# MCU_hall_crossboard_1_1.net
KiCad netlist of a schematic drawn in Altium Designer
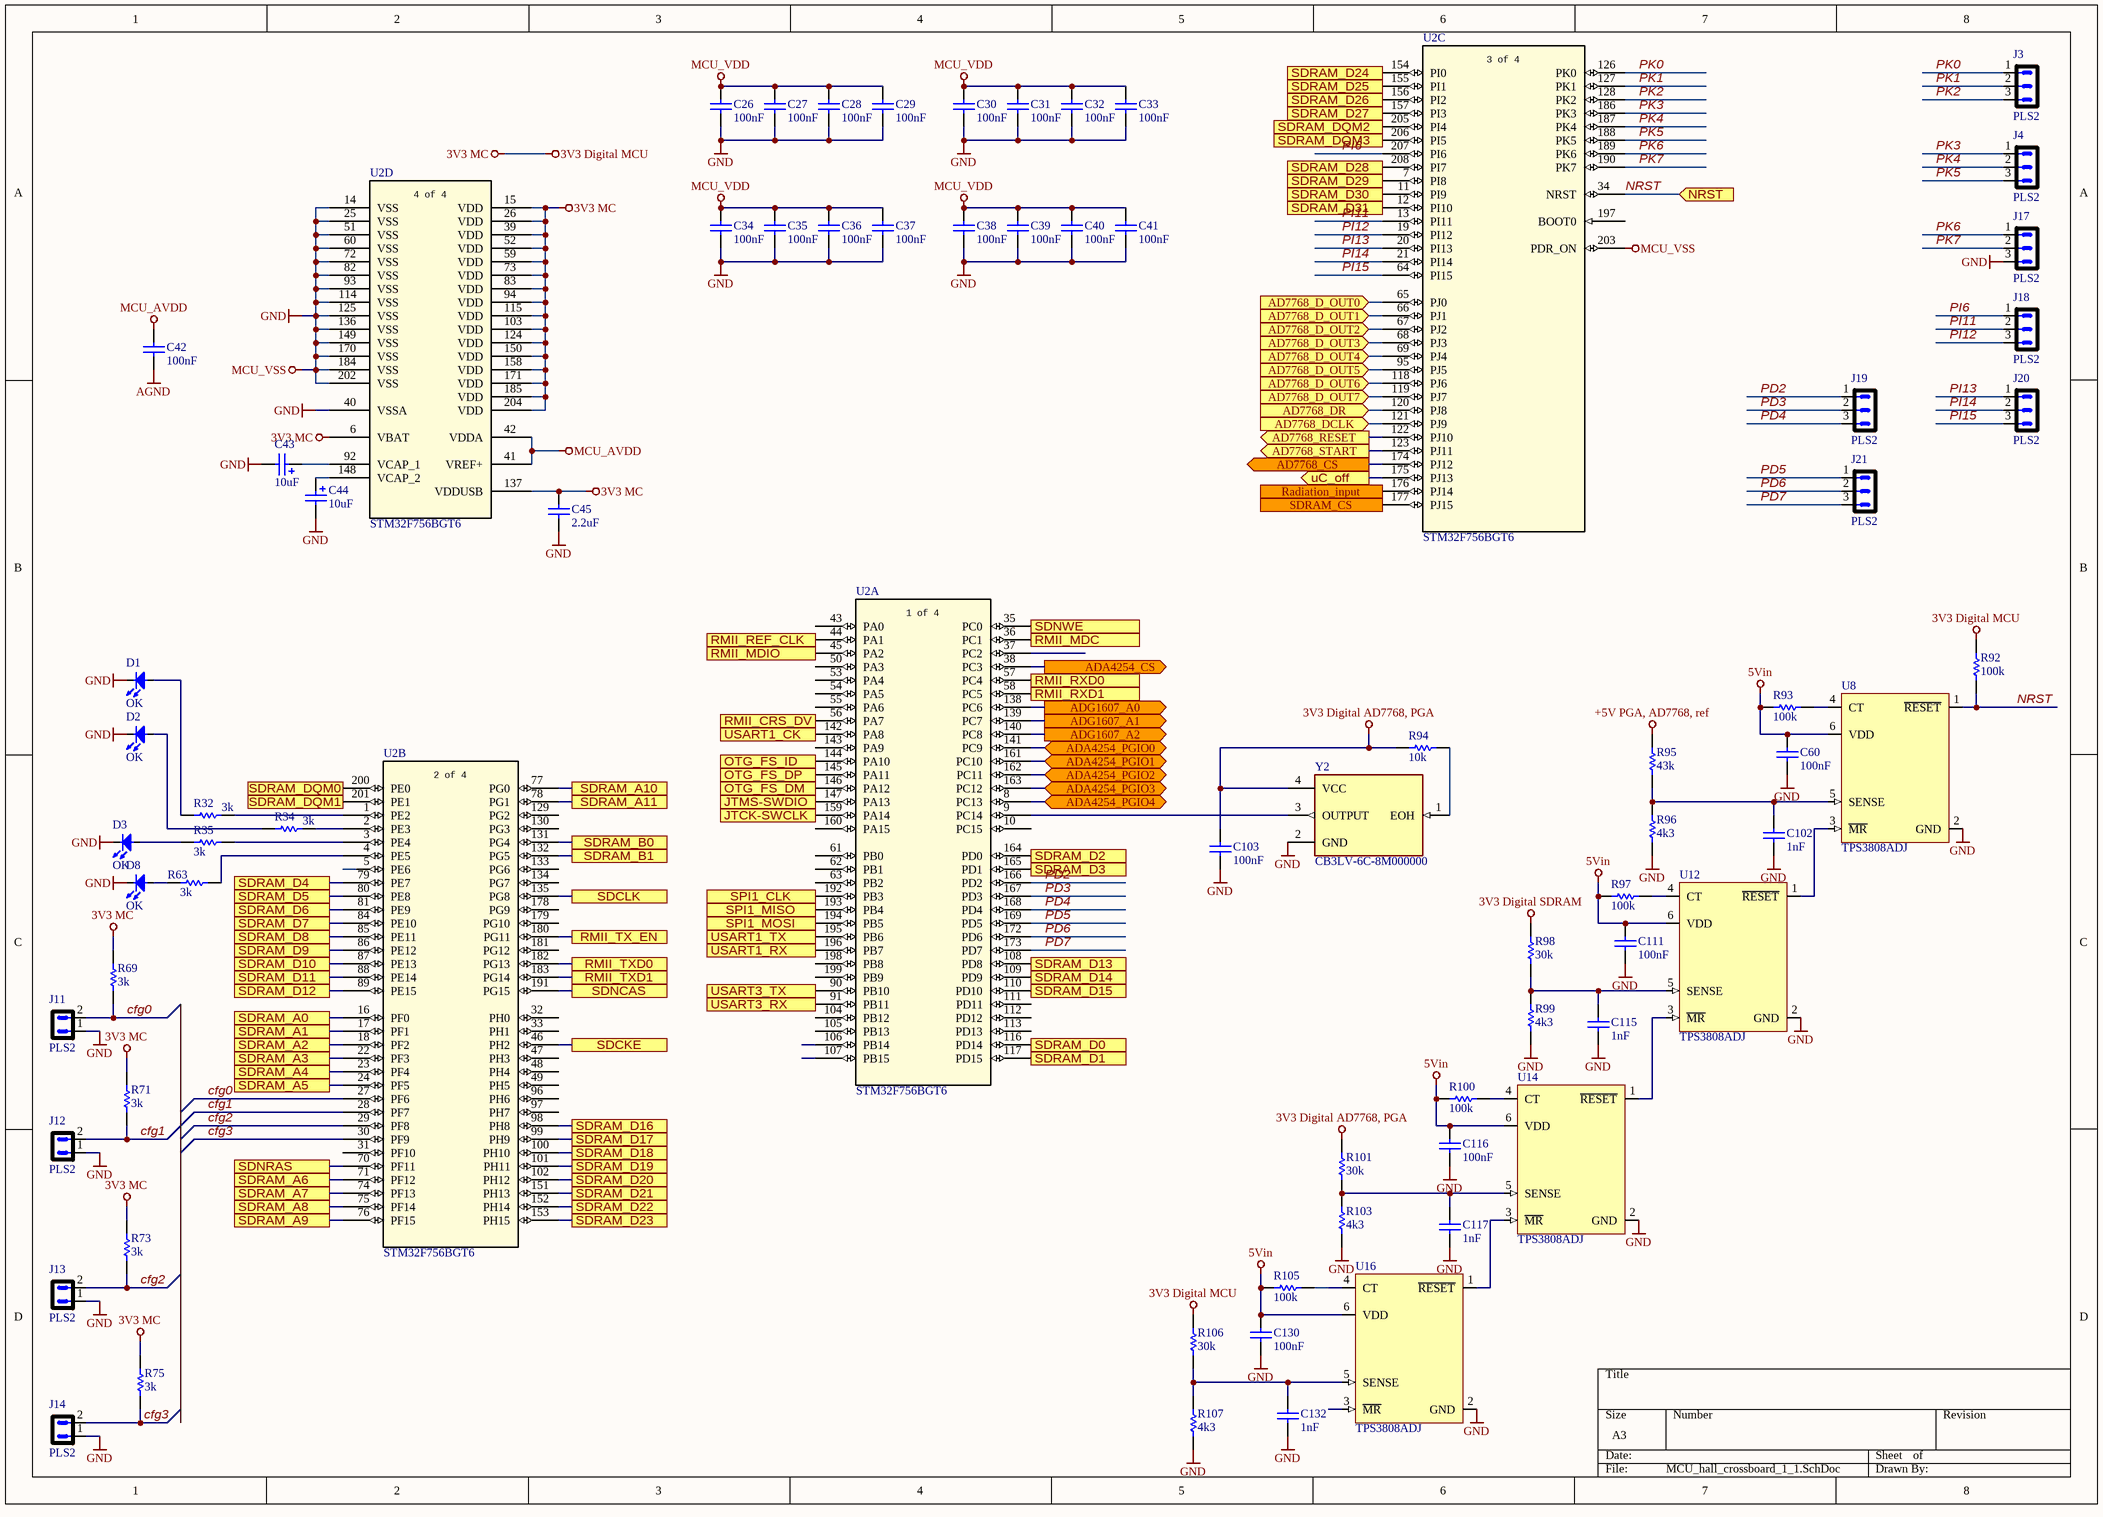
[diagram p0: MCU_hall_crossboard_1_1.SchDoc]

(export (version "E")
  (design (tool "Eeschema 10.0.6"))
  (components
    (comp (ref "C26")
      (value "100nF")
      (footprint "hall_crossboard_1_1_library:0603C")
      (description "Capacitor 0402 / 0603 / 0805")
      (libsource (lib "hall_crossboard_1_1_library") (part "Capacitor_ST"))
    )
    (comp (ref "C27")
      (value "100nF")
      (footprint "hall_crossboard_1_1_library:0603C")
      (description "Capacitor 0402 / 0603 / 0805")
      (libsource (lib "hall_crossboard_1_1_library") (part "Capacitor_ST"))
    )
    (comp (ref "C28")
      (value "100nF")
      (footprint "hall_crossboard_1_1_library:0603C")
      (description "Capacitor 0402 / 0603 / 0805")
      (libsource (lib "hall_crossboard_1_1_library") (part "Capacitor_ST"))
    )
    (comp (ref "C29")
      (value "100nF")
      (footprint "hall_crossboard_1_1_library:0603C")
      (description "Capacitor 0402 / 0603 / 0805")
      (libsource (lib "hall_crossboard_1_1_library") (part "Capacitor_ST"))
    )
    (comp (ref "C30")
      (value "100nF")
      (footprint "hall_crossboard_1_1_library:0603C")
      (description "Capacitor 0402 / 0603 / 0805")
      (libsource (lib "hall_crossboard_1_1_library") (part "Capacitor_ST"))
    )
    (comp (ref "C31")
      (value "100nF")
      (footprint "hall_crossboard_1_1_library:0603C")
      (description "Capacitor 0402 / 0603 / 0805")
      (libsource (lib "hall_crossboard_1_1_library") (part "Capacitor_ST"))
    )
    (comp (ref "C32")
      (value "100nF")
      (footprint "hall_crossboard_1_1_library:0603C")
      (description "Capacitor 0402 / 0603 / 0805")
      (libsource (lib "hall_crossboard_1_1_library") (part "Capacitor_ST"))
    )
    (comp (ref "C33")
      (value "100nF")
      (footprint "hall_crossboard_1_1_library:0603C")
      (description "Capacitor 0402 / 0603 / 0805")
      (libsource (lib "hall_crossboard_1_1_library") (part "Capacitor_ST"))
    )
    (comp (ref "C34")
      (value "100nF")
      (footprint "hall_crossboard_1_1_library:0603C")
      (description "Capacitor 0402 / 0603 / 0805")
      (libsource (lib "hall_crossboard_1_1_library") (part "Capacitor_ST"))
    )
    (comp (ref "C35")
      (value "100nF")
      (footprint "hall_crossboard_1_1_library:0603C")
      (description "Capacitor 0402 / 0603 / 0805")
      (libsource (lib "hall_crossboard_1_1_library") (part "Capacitor_ST"))
    )
    (comp (ref "C36")
      (value "100nF")
      (footprint "hall_crossboard_1_1_library:0603C")
      (description "Capacitor 0402 / 0603 / 0805")
      (libsource (lib "hall_crossboard_1_1_library") (part "Capacitor_ST"))
    )
    (comp (ref "C37")
      (value "100nF")
      (footprint "hall_crossboard_1_1_library:0603C")
      (description "Capacitor 0402 / 0603 / 0805")
      (libsource (lib "hall_crossboard_1_1_library") (part "Capacitor_ST"))
    )
    (comp (ref "C38")
      (value "100nF")
      (footprint "hall_crossboard_1_1_library:0603C")
      (description "Capacitor 0402 / 0603 / 0805")
      (libsource (lib "hall_crossboard_1_1_library") (part "Capacitor_ST"))
    )
    (comp (ref "C39")
      (value "100nF")
      (footprint "hall_crossboard_1_1_library:0603C")
      (description "Capacitor 0402 / 0603 / 0805")
      (libsource (lib "hall_crossboard_1_1_library") (part "Capacitor_ST"))
    )
    (comp (ref "C40")
      (value "100nF")
      (footprint "hall_crossboard_1_1_library:0603C")
      (description "Capacitor 0402 / 0603 / 0805")
      (libsource (lib "hall_crossboard_1_1_library") (part "Capacitor_ST"))
    )
    (comp (ref "C41")
      (value "100nF")
      (footprint "hall_crossboard_1_1_library:0603C")
      (description "Capacitor 0402 / 0603 / 0805")
      (libsource (lib "hall_crossboard_1_1_library") (part "Capacitor_ST"))
    )
    (comp (ref "C42")
      (value "100nF")
      (footprint "hall_crossboard_1_1_library:0603C")
      (description "Capacitor 0402 / 0603 / 0805")
      (libsource (lib "hall_crossboard_1_1_library") (part "Capacitor_ST"))
    )
    (comp (ref "C43")
      (value "10uF")
      (footprint "hall_crossboard_1_1_library:0805C")
      (description "Polarized Capacitor,10uF,10V,10%,typeA,VISHAY")
      (libsource (lib "hall_crossboard_1_1_library") (part "Cap_10uF_POL_10%_TANA"))
    )
    (comp (ref "C44")
      (value "10uF")
      (footprint "hall_crossboard_1_1_library:0805C")
      (description "Polarized Capacitor,10uF,10V,10%,typeA,VISHAY")
      (libsource (lib "hall_crossboard_1_1_library") (part "Cap_10uF_POL_10%_TANA"))
    )
    (comp (ref "C45")
      (value "2.2uF")
      (footprint "hall_crossboard_1_1_library:0805C")
      (description "Capacitor 0402 / 0603 / 0805")
      (libsource (lib "hall_crossboard_1_1_library") (part "Capacitor_ST"))
    )
    (comp (ref "C60")
      (value "100nF")
      (footprint "hall_crossboard_1_1_library:0603C")
      (description "Capacitor 0402 / 0603 / 0805")
      (libsource (lib "hall_crossboard_1_1_library") (part "Capacitor_ST"))
    )
    (comp (ref "C102")
      (value "1nF")
      (footprint "hall_crossboard_1_1_library:0603C")
      (description "Capacitor 0402 / 0603 / 0805")
      (libsource (lib "hall_crossboard_1_1_library") (part "Capacitor_ST"))
    )
    (comp (ref "C103")
      (value "100nF")
      (footprint "hall_crossboard_1_1_library:0603C")
      (description "Capacitor 0402 / 0603 / 0805")
      (libsource (lib "hall_crossboard_1_1_library") (part "Capacitor_ST"))
    )
    (comp (ref "C111")
      (value "100nF")
      (footprint "hall_crossboard_1_1_library:0603C")
      (description "Capacitor 0402 / 0603 / 0805")
      (libsource (lib "hall_crossboard_1_1_library") (part "Capacitor_ST"))
    )
    (comp (ref "C115")
      (value "1nF")
      (footprint "hall_crossboard_1_1_library:0603C")
      (description "Capacitor 0402 / 0603 / 0805")
      (libsource (lib "hall_crossboard_1_1_library") (part "Capacitor_ST"))
    )
    (comp (ref "C116")
      (value "100nF")
      (footprint "hall_crossboard_1_1_library:0603C")
      (description "Capacitor 0402 / 0603 / 0805")
      (libsource (lib "hall_crossboard_1_1_library") (part "Capacitor_ST"))
    )
    (comp (ref "C117")
      (value "1nF")
      (footprint "hall_crossboard_1_1_library:0603C")
      (description "Capacitor 0402 / 0603 / 0805")
      (libsource (lib "hall_crossboard_1_1_library") (part "Capacitor_ST"))
    )
    (comp (ref "C130")
      (value "100nF")
      (footprint "hall_crossboard_1_1_library:0603C")
      (description "Capacitor 0402 / 0603 / 0805")
      (libsource (lib "hall_crossboard_1_1_library") (part "Capacitor_ST"))
    )
    (comp (ref "C132")
      (value "1nF")
      (footprint "hall_crossboard_1_1_library:0603C")
      (description "Capacitor 0402 / 0603 / 0805")
      (libsource (lib "hall_crossboard_1_1_library") (part "Capacitor_ST"))
    )
    (comp (ref "D1")
      (value "OK")
      (footprint "LED0603")
      (description "Чип светодиод 0603")
      (libsource (lib "schematic_hall_crossboard_1_1_library") (part "LED0603"))
    )
    (comp (ref "D2")
      (value "OK")
      (footprint "LED0603")
      (description "Чип светодиод 0603")
      (libsource (lib "schematic_hall_crossboard_1_1_library") (part "LED0603"))
    )
    (comp (ref "D3")
      (value "OK")
      (footprint "LED0603")
      (description "Чип светодиод 0603")
      (libsource (lib "schematic_hall_crossboard_1_1_library") (part "LED0603"))
    )
    (comp (ref "D8")
      (value "OK")
      (footprint "LED0603")
      (description "Чип светодиод 0603")
      (libsource (lib "schematic_hall_crossboard_1_1_library") (part "LED0603"))
    )
    (comp (ref "J3")
      (value "PLS2")
      (footprint "COMATEL_385.0358.1.03.400")
      (description "PLS3")
      (libsource (lib "hall_crossboard_1_1") (part "PLS3"))
    )
    (comp (ref "J4")
      (value "PLS2")
      (footprint "COMATEL_385.0358.1.03.400")
      (description "PLS3")
      (libsource (lib "hall_crossboard_1_1") (part "PLS3"))
    )
    (comp (ref "J11")
      (value "PLS2")
      (footprint "SAMTEC_TSW-102-23-L-S")
      (libsource (lib "hall_crossboard_1_1_library") (part "PLS2"))
    )
    (comp (ref "J12")
      (value "PLS2")
      (footprint "SAMTEC_TSW-102-23-L-S")
      (libsource (lib "hall_crossboard_1_1_library") (part "PLS2"))
    )
    (comp (ref "J13")
      (value "PLS2")
      (footprint "SAMTEC_TSW-102-23-L-S")
      (libsource (lib "hall_crossboard_1_1_library") (part "PLS2"))
    )
    (comp (ref "J14")
      (value "PLS2")
      (footprint "SAMTEC_TSW-102-23-L-S")
      (libsource (lib "hall_crossboard_1_1_library") (part "PLS2"))
    )
    (comp (ref "J17")
      (value "PLS2")
      (footprint "COMATEL_385.0358.1.03.400")
      (description "PLS3")
      (libsource (lib "hall_crossboard_1_1") (part "PLS3"))
    )
    (comp (ref "J18")
      (value "PLS2")
      (footprint "COMATEL_385.0358.1.03.400")
      (description "PLS3")
      (libsource (lib "hall_crossboard_1_1") (part "PLS3"))
    )
    (comp (ref "J19")
      (value "PLS2")
      (footprint "COMATEL_385.0358.1.03.400")
      (description "PLS3")
      (libsource (lib "hall_crossboard_1_1") (part "PLS3"))
    )
    (comp (ref "J20")
      (value "PLS2")
      (footprint "COMATEL_385.0358.1.03.400")
      (description "PLS3")
      (libsource (lib "hall_crossboard_1_1") (part "PLS3"))
    )
    (comp (ref "J21")
      (value "PLS2")
      (footprint "COMATEL_385.0358.1.03.400")
      (description "PLS3")
      (libsource (lib "hall_crossboard_1_1") (part "PLS3"))
    )
    (comp (ref "R32")
      (value "3k")
      (footprint "0603R")
      (description "Resistor 0402 / 0603 / 0805")
      (libsource (lib "hall_crossboard_1_1_library") (part "Resistor_ST"))
    )
    (comp (ref "R34")
      (value "3k")
      (footprint "0603R")
      (description "Resistor 0402 / 0603 / 0805")
      (libsource (lib "hall_crossboard_1_1_library") (part "Resistor_ST"))
    )
    (comp (ref "R35")
      (value "3k")
      (footprint "0603R")
      (description "Resistor 0402 / 0603 / 0805")
      (libsource (lib "hall_crossboard_1_1_library") (part "Resistor_ST"))
    )
    (comp (ref "R63")
      (value "3k")
      (footprint "0603R")
      (description "Resistor 0402 / 0603 / 0805")
      (libsource (lib "hall_crossboard_1_1_library") (part "Resistor_ST"))
    )
    (comp (ref "R69")
      (value "3k")
      (footprint "0603R")
      (description "Resistor 0402 / 0603 / 0805")
      (libsource (lib "hall_crossboard_1_1_library") (part "Resistor_ST"))
    )
    (comp (ref "R71")
      (value "3k")
      (footprint "0603R")
      (description "Resistor 0402 / 0603 / 0805")
      (libsource (lib "hall_crossboard_1_1_library") (part "Resistor_ST"))
    )
    (comp (ref "R73")
      (value "3k")
      (footprint "0603R")
      (description "Resistor 0402 / 0603 / 0805")
      (libsource (lib "hall_crossboard_1_1_library") (part "Resistor_ST"))
    )
    (comp (ref "R75")
      (value "3k")
      (footprint "0603R")
      (description "Resistor 0402 / 0603 / 0805")
      (libsource (lib "hall_crossboard_1_1_library") (part "Resistor_ST"))
    )
    (comp (ref "R92")
      (value "100k")
      (footprint "0805R")
      (description "Resistor 0402 / 0603 / 0805")
      (libsource (lib "hall_crossboard_1_1_library") (part "Resistor_ST"))
    )
    (comp (ref "R93")
      (value "100k")
      (footprint "0805R")
      (description "Resistor 0402 / 0603 / 0805")
      (libsource (lib "hall_crossboard_1_1_library") (part "Resistor_ST"))
    )
    (comp (ref "R94")
      (value "10k")
      (footprint "0805R")
      (description "Resistor 0402 / 0603 / 0805 c2")
      (libsource (lib "hall_crossboard_1_1") (part "Resistor_ST"))
    )
    (comp (ref "R95")
      (value "43k")
      (footprint "0805R")
      (description "Resistor 0402 / 0603 / 0805")
      (libsource (lib "hall_crossboard_1_1_library") (part "Resistor_ST"))
    )
    (comp (ref "R96")
      (value "4k3")
      (footprint "0805R")
      (description "Resistor 0402 / 0603 / 0805")
      (libsource (lib "hall_crossboard_1_1_library") (part "Resistor_ST"))
    )
    (comp (ref "R97")
      (value "100k")
      (footprint "0805R")
      (description "Resistor 0402 / 0603 / 0805")
      (libsource (lib "hall_crossboard_1_1_library") (part "Resistor_ST"))
    )
    (comp (ref "R98")
      (value "30k")
      (footprint "0805R")
      (description "Resistor 0402 / 0603 / 0805")
      (libsource (lib "hall_crossboard_1_1_library") (part "Resistor_ST"))
    )
    (comp (ref "R99")
      (value "4k3")
      (footprint "0805R")
      (description "Resistor 0402 / 0603 / 0805")
      (libsource (lib "hall_crossboard_1_1_library") (part "Resistor_ST"))
    )
    (comp (ref "R100")
      (value "100k")
      (footprint "0805R")
      (description "Resistor 0402 / 0603 / 0805")
      (libsource (lib "hall_crossboard_1_1_library") (part "Resistor_ST"))
    )
    (comp (ref "R101")
      (value "30k")
      (footprint "0805R")
      (description "Resistor 0402 / 0603 / 0805")
      (libsource (lib "hall_crossboard_1_1_library") (part "Resistor_ST"))
    )
    (comp (ref "R103")
      (value "4k3")
      (footprint "0805R")
      (description "Resistor 0402 / 0603 / 0805")
      (libsource (lib "hall_crossboard_1_1_library") (part "Resistor_ST"))
    )
    (comp (ref "R105")
      (value "100k")
      (footprint "0805R")
      (description "Resistor 0402 / 0603 / 0805")
      (libsource (lib "hall_crossboard_1_1_library") (part "Resistor_ST"))
    )
    (comp (ref "R106")
      (value "30k")
      (footprint "0805R")
      (description "Resistor 0402 / 0603 / 0805")
      (libsource (lib "hall_crossboard_1_1_library") (part "Resistor_ST"))
    )
    (comp (ref "R107")
      (value "4k3")
      (footprint "0805R")
      (description "Resistor 0402 / 0603 / 0805")
      (libsource (lib "hall_crossboard_1_1_library") (part "Resistor_ST"))
    )
    (comp (ref "U2")
      (value "STM32F756BGT6")
      (footprint "footprint_hall_crossboard_1_1_library:QFP50P3000X3000X160-208N")
      (description "No Description Available")
      (libsource (lib "schematic_hall_crossboard_1_1_library") (part "STM32F756BGT6"))
    )
    (comp (ref "U8")
      (value "TPS3808ADJ")
      (footprint "footprint_hall_crossboard_1_1_library:SOT95P270X145-6N")
      (description "Supervisory Circuit. Low-Quiescent-Current, Programmable-Delay")
      (libsource (lib "schematic_hall_crossboard_1_1_library") (part "TPS3808"))
    )
    (comp (ref "U12")
      (value "TPS3808ADJ")
      (footprint "footprint_hall_crossboard_1_1_library:SOT95P270X145-6N")
      (description "Supervisory Circuit. Low-Quiescent-Current, Programmable-Delay")
      (libsource (lib "schematic_hall_crossboard_1_1_library") (part "TPS3808"))
    )
    (comp (ref "U14")
      (value "TPS3808ADJ")
      (footprint "footprint_hall_crossboard_1_1_library:SOT95P270X145-6N")
      (description "Supervisory Circuit. Low-Quiescent-Current, Programmable-Delay")
      (libsource (lib "schematic_hall_crossboard_1_1_library") (part "TPS3808"))
    )
    (comp (ref "U16")
      (value "TPS3808ADJ")
      (footprint "footprint_hall_crossboard_1_1_library:SOT95P270X145-6N")
      (description "Supervisory Circuit. Low-Quiescent-Current, Programmable-Delay")
      (libsource (lib "schematic_hall_crossboard_1_1_library") (part "TPS3808"))
    )
    (comp (ref "Y2")
      (value "CB3LV-6C-8M000000")
      (footprint "OSC_CB3LV-6C-8M000000")
      (description "8 MHz XO (Standard) HCMOS, TTL Oscillator 3.3V Enable/Disable 4-SMD, No Lead")
      (fields (field (name "MF") "CTS-Frequency Controls"))
      (libsource (lib "hall_crossboard_1_1") (part "CB3LV-6C-8M000000"))
    )
  )
  (nets
    (net (code "1") (name "+5V PGA, AD7768, ref") (class "Default")
      (node (ref "R95") (pin "2") (pinfunction "2_2") (pintype "passive"))
    )
    (net (code "2") (name "/AD7768_CS") (class "Default")
      (node (ref "U2") (pin "174") (pinfunction "PJ12_174") (pintype "bidirectional"))
    )
    (net (code "3") (name "/AD7768_DCLK") (class "Default")
      (node (ref "U2") (pin "121") (pinfunction "PJ9_121") (pintype "bidirectional"))
    )
    (net (code "4") (name "/AD7768_DR") (class "Default")
      (node (ref "U2") (pin "120") (pinfunction "PJ8_120") (pintype "bidirectional"))
    )
    (net (code "5") (name "/AD7768_D_OUT0") (class "Default")
      (node (ref "U2") (pin "65") (pinfunction "PJ0_65") (pintype "bidirectional"))
    )
    (net (code "6") (name "/AD7768_D_OUT1") (class "Default")
      (node (ref "U2") (pin "66") (pinfunction "PJ1_66") (pintype "bidirectional"))
    )
    (net (code "7") (name "/AD7768_D_OUT2") (class "Default")
      (node (ref "U2") (pin "67") (pinfunction "PJ2_67") (pintype "bidirectional"))
    )
    (net (code "8") (name "/AD7768_D_OUT3") (class "Default")
      (node (ref "U2") (pin "68") (pinfunction "PJ3_68") (pintype "bidirectional"))
    )
    (net (code "9") (name "/AD7768_D_OUT4") (class "Default")
      (node (ref "U2") (pin "69") (pinfunction "PJ4_69") (pintype "bidirectional"))
    )
    (net (code "10") (name "/AD7768_D_OUT5") (class "Default")
      (node (ref "U2") (pin "95") (pinfunction "PJ5_95") (pintype "bidirectional"))
    )
    (net (code "11") (name "/AD7768_D_OUT6") (class "Default")
      (node (ref "U2") (pin "118") (pinfunction "PJ6_118") (pintype "bidirectional"))
    )
    (net (code "12") (name "/AD7768_D_OUT7") (class "Default")
      (node (ref "U2") (pin "119") (pinfunction "PJ7_119") (pintype "bidirectional"))
    )
    (net (code "13") (name "/AD7768_RESET") (class "Default")
      (node (ref "U2") (pin "122") (pinfunction "PJ10_122") (pintype "bidirectional"))
    )
    (net (code "14") (name "/AD7768_START") (class "Default")
      (node (ref "U2") (pin "123") (pinfunction "PJ11_123") (pintype "bidirectional"))
    )
    (net (code "15") (name "/ADA4254_CS") (class "Default")
      (node (ref "U2") (pin "38") (pinfunction "PC3_38") (pintype "bidirectional"))
    )
    (net (code "16") (name "/ADA4254_PGIO0") (class "Default")
      (node (ref "U2") (pin "141") (pinfunction "PC9_141") (pintype "bidirectional"))
    )
    (net (code "17") (name "/ADA4254_PGIO1") (class "Default")
      (node (ref "U2") (pin "161") (pinfunction "PC10_161") (pintype "bidirectional"))
    )
    (net (code "18") (name "/ADA4254_PGIO2") (class "Default")
      (node (ref "U2") (pin "162") (pinfunction "PC11_162") (pintype "bidirectional"))
    )
    (net (code "19") (name "/ADA4254_PGIO3") (class "Default")
      (node (ref "U2") (pin "163") (pinfunction "PC12_163") (pintype "bidirectional"))
    )
    (net (code "20") (name "/ADA4254_PGIO4") (class "Default")
      (node (ref "U2") (pin "8") (pinfunction "PC13_8") (pintype "bidirectional"))
    )
    (net (code "21") (name "/ADG1607_A0") (class "Default")
      (node (ref "U2") (pin "138") (pinfunction "PC6_138") (pintype "bidirectional"))
    )
    (net (code "22") (name "/ADG1607_A1") (class "Default")
      (node (ref "U2") (pin "139") (pinfunction "PC7_139") (pintype "bidirectional"))
    )
    (net (code "23") (name "/ADG1607_A2") (class "Default")
      (node (ref "U2") (pin "140") (pinfunction "PC8_140") (pintype "bidirectional"))
    )
    (net (code "24") (name "/JTCK-SWCLK") (class "Default")
      (node (ref "U2") (pin "159") (pinfunction "PA14_159") (pintype "bidirectional"))
    )
    (net (code "25") (name "/JTMS-SWDIO") (class "Default")
      (node (ref "U2") (pin "147") (pinfunction "PA13_147") (pintype "bidirectional"))
    )
    (net (code "26") (name "/NRST") (class "Default")
      (node (ref "R92") (pin "1") (pinfunction "1_1") (pintype "passive"))
      (node (ref "U2") (pin "34") (pinfunction "NRST_34") (pintype "bidirectional"))
      (node (ref "U8") (pin "1") (pinfunction "~{RESET}_1") (pintype "open_collector"))
    )
    (net (code "27") (name "/OTG_FS_DM") (class "Default")
      (node (ref "U2") (pin "146") (pinfunction "PA12_146") (pintype "bidirectional"))
    )
    (net (code "28") (name "/OTG_FS_DP") (class "Default")
      (node (ref "U2") (pin "145") (pinfunction "PA11_145") (pintype "bidirectional"))
    )
    (net (code "29") (name "/OTG_FS_ID") (class "Default")
      (node (ref "U2") (pin "144") (pinfunction "PA10_144") (pintype "bidirectional"))
    )
    (net (code "30") (name "/PD2") (class "Default")
      (node (ref "J19") (pin "1") (pinfunction "1_1") (pintype "bidirectional"))
      (node (ref "U2") (pin "166") (pinfunction "PD2_166") (pintype "bidirectional"))
    )
    (net (code "31") (name "/PD3") (class "Default")
      (node (ref "J19") (pin "2") (pinfunction "2_2") (pintype "bidirectional"))
      (node (ref "U2") (pin "167") (pinfunction "PD3_167") (pintype "bidirectional"))
    )
    (net (code "32") (name "/PD4") (class "Default")
      (node (ref "J19") (pin "3") (pinfunction "3_3") (pintype "bidirectional"))
      (node (ref "U2") (pin "168") (pinfunction "PD4_168") (pintype "bidirectional"))
    )
    (net (code "33") (name "/PD5") (class "Default")
      (node (ref "J21") (pin "1") (pinfunction "1_1") (pintype "bidirectional"))
      (node (ref "U2") (pin "169") (pinfunction "PD5_169") (pintype "bidirectional"))
    )
    (net (code "34") (name "/PD6") (class "Default")
      (node (ref "J21") (pin "2") (pinfunction "2_2") (pintype "bidirectional"))
      (node (ref "U2") (pin "172") (pinfunction "PD6_172") (pintype "bidirectional"))
    )
    (net (code "35") (name "/PD7") (class "Default")
      (node (ref "J21") (pin "3") (pinfunction "3_3") (pintype "bidirectional"))
      (node (ref "U2") (pin "173") (pinfunction "PD7_173") (pintype "bidirectional"))
    )
    (net (code "36") (name "/PI6") (class "Default")
      (node (ref "J18") (pin "1") (pinfunction "1_1") (pintype "bidirectional"))
      (node (ref "U2") (pin "207") (pinfunction "PI6_207") (pintype "bidirectional"))
    )
    (net (code "37") (name "/PI11") (class "Default")
      (node (ref "J18") (pin "2") (pinfunction "2_2") (pintype "bidirectional"))
      (node (ref "U2") (pin "13") (pinfunction "PI11_13") (pintype "bidirectional"))
    )
    (net (code "38") (name "/PI12") (class "Default")
      (node (ref "J18") (pin "3") (pinfunction "3_3") (pintype "bidirectional"))
      (node (ref "U2") (pin "19") (pinfunction "PI12_19") (pintype "bidirectional"))
    )
    (net (code "39") (name "/PI13") (class "Default")
      (node (ref "J20") (pin "1") (pinfunction "1_1") (pintype "bidirectional"))
      (node (ref "U2") (pin "20") (pinfunction "PI13_20") (pintype "bidirectional"))
    )
    (net (code "40") (name "/PI14") (class "Default")
      (node (ref "J20") (pin "2") (pinfunction "2_2") (pintype "bidirectional"))
      (node (ref "U2") (pin "21") (pinfunction "PI14_21") (pintype "bidirectional"))
    )
    (net (code "41") (name "/PI15") (class "Default")
      (node (ref "J20") (pin "3") (pinfunction "3_3") (pintype "bidirectional"))
      (node (ref "U2") (pin "64") (pinfunction "PI15_64") (pintype "bidirectional"))
    )
    (net (code "42") (name "/PK0") (class "Default")
      (node (ref "J3") (pin "1") (pinfunction "1_1") (pintype "bidirectional"))
      (node (ref "U2") (pin "126") (pinfunction "PK0_126") (pintype "bidirectional"))
    )
    (net (code "43") (name "/PK1") (class "Default")
      (node (ref "J3") (pin "2") (pinfunction "2_2") (pintype "bidirectional"))
      (node (ref "U2") (pin "127") (pinfunction "PK1_127") (pintype "bidirectional"))
    )
    (net (code "44") (name "/PK2") (class "Default")
      (node (ref "J3") (pin "3") (pinfunction "3_3") (pintype "bidirectional"))
      (node (ref "U2") (pin "128") (pinfunction "PK2_128") (pintype "bidirectional"))
    )
    (net (code "45") (name "/PK3") (class "Default")
      (node (ref "J4") (pin "1") (pinfunction "1_1") (pintype "bidirectional"))
      (node (ref "U2") (pin "186") (pinfunction "PK3_186") (pintype "bidirectional"))
    )
    (net (code "46") (name "/PK4") (class "Default")
      (node (ref "J4") (pin "2") (pinfunction "2_2") (pintype "bidirectional"))
      (node (ref "U2") (pin "187") (pinfunction "PK4_187") (pintype "bidirectional"))
    )
    (net (code "47") (name "/PK5") (class "Default")
      (node (ref "J4") (pin "3") (pinfunction "3_3") (pintype "bidirectional"))
      (node (ref "U2") (pin "188") (pinfunction "PK5_188") (pintype "bidirectional"))
    )
    (net (code "48") (name "/PK6") (class "Default")
      (node (ref "J17") (pin "1") (pinfunction "1_1") (pintype "bidirectional"))
      (node (ref "U2") (pin "189") (pinfunction "PK6_189") (pintype "bidirectional"))
    )
    (net (code "49") (name "/PK7") (class "Default")
      (node (ref "J17") (pin "2") (pinfunction "2_2") (pintype "bidirectional"))
      (node (ref "U2") (pin "190") (pinfunction "PK7_190") (pintype "bidirectional"))
    )
    (net (code "50") (name "/RMII_CRS_DV") (class "Default")
      (node (ref "U2") (pin "56") (pinfunction "PA7_56") (pintype "bidirectional"))
    )
    (net (code "51") (name "/RMII_MDC") (class "Default")
      (node (ref "U2") (pin "36") (pinfunction "PC1_36") (pintype "bidirectional"))
    )
    (net (code "52") (name "/RMII_MDIO") (class "Default")
      (node (ref "U2") (pin "45") (pinfunction "PA2_45") (pintype "bidirectional"))
    )
    (net (code "53") (name "/RMII_REF_CLK") (class "Default")
      (node (ref "U2") (pin "44") (pinfunction "PA1_44") (pintype "bidirectional"))
    )
    (net (code "54") (name "/RMII_RXD0") (class "Default")
      (node (ref "U2") (pin "57") (pinfunction "PC4_57") (pintype "bidirectional"))
    )
    (net (code "55") (name "/RMII_RXD1") (class "Default")
      (node (ref "U2") (pin "58") (pinfunction "PC5_58") (pintype "bidirectional"))
    )
    (net (code "56") (name "/RMII_TXD0") (class "Default")
      (node (ref "U2") (pin "182") (pinfunction "PG13_182") (pintype "bidirectional"))
    )
    (net (code "57") (name "/RMII_TXD1") (class "Default")
      (node (ref "U2") (pin "183") (pinfunction "PG14_183") (pintype "bidirectional"))
    )
    (net (code "58") (name "/RMII_TX_EN") (class "Default")
      (node (ref "U2") (pin "180") (pinfunction "PG11_180") (pintype "bidirectional"))
    )
    (net (code "59") (name "/Radiation_input") (class "Default")
      (node (ref "U2") (pin "176") (pinfunction "PJ14_176") (pintype "bidirectional"))
    )
    (net (code "60") (name "/SDCKE") (class "Default")
      (node (ref "U2") (pin "46") (pinfunction "PH2_46") (pintype "bidirectional"))
    )
    (net (code "61") (name "/SDCLK") (class "Default")
      (node (ref "U2") (pin "135") (pinfunction "PG8_135") (pintype "bidirectional"))
    )
    (net (code "62") (name "/SDNCAS") (class "Default")
      (node (ref "U2") (pin "191") (pinfunction "PG15_191") (pintype "bidirectional"))
    )
    (net (code "63") (name "/SDNRAS") (class "Default")
      (node (ref "U2") (pin "70") (pinfunction "PF11_70") (pintype "bidirectional"))
    )
    (net (code "64") (name "/SDNWE") (class "Default")
      (node (ref "U2") (pin "35") (pinfunction "PC0_35") (pintype "bidirectional"))
    )
    (net (code "65") (name "/SDRAM_A0") (class "Default")
      (node (ref "U2") (pin "16") (pinfunction "PF0_16") (pintype "bidirectional"))
    )
    (net (code "66") (name "/SDRAM_A1") (class "Default")
      (node (ref "U2") (pin "17") (pinfunction "PF1_17") (pintype "bidirectional"))
    )
    (net (code "67") (name "/SDRAM_A2") (class "Default")
      (node (ref "U2") (pin "18") (pinfunction "PF2_18") (pintype "bidirectional"))
    )
    (net (code "68") (name "/SDRAM_A3") (class "Default")
      (node (ref "U2") (pin "22") (pinfunction "PF3_22") (pintype "bidirectional"))
    )
    (net (code "69") (name "/SDRAM_A4") (class "Default")
      (node (ref "U2") (pin "23") (pinfunction "PF4_23") (pintype "bidirectional"))
    )
    (net (code "70") (name "/SDRAM_A5") (class "Default")
      (node (ref "U2") (pin "24") (pinfunction "PF5_24") (pintype "bidirectional"))
    )
    (net (code "71") (name "/SDRAM_A6") (class "Default")
      (node (ref "U2") (pin "71") (pinfunction "PF12_71") (pintype "bidirectional"))
    )
    (net (code "72") (name "/SDRAM_A7") (class "Default")
      (node (ref "U2") (pin "74") (pinfunction "PF13_74") (pintype "bidirectional"))
    )
    (net (code "73") (name "/SDRAM_A8") (class "Default")
      (node (ref "U2") (pin "75") (pinfunction "PF14_75") (pintype "bidirectional"))
    )
    (net (code "74") (name "/SDRAM_A9") (class "Default")
      (node (ref "U2") (pin "76") (pinfunction "PF15_76") (pintype "bidirectional"))
    )
    (net (code "75") (name "/SDRAM_A10") (class "Default")
      (node (ref "U2") (pin "77") (pinfunction "PG0_77") (pintype "bidirectional"))
    )
    (net (code "76") (name "/SDRAM_A11") (class "Default")
      (node (ref "U2") (pin "78") (pinfunction "PG1_78") (pintype "bidirectional"))
    )
    (net (code "77") (name "/SDRAM_B0") (class "Default")
      (node (ref "U2") (pin "131") (pinfunction "PG4_131") (pintype "bidirectional"))
    )
    (net (code "78") (name "/SDRAM_B1") (class "Default")
      (node (ref "U2") (pin "132") (pinfunction "PG5_132") (pintype "bidirectional"))
    )
    (net (code "79") (name "/SDRAM_CS") (class "Default")
      (node (ref "U2") (pin "177") (pinfunction "PJ15_177") (pintype "bidirectional"))
    )
    (net (code "80") (name "/SDRAM_D0") (class "Default")
      (node (ref "U2") (pin "116") (pinfunction "PD14_116") (pintype "bidirectional"))
    )
    (net (code "81") (name "/SDRAM_D1") (class "Default")
      (node (ref "U2") (pin "117") (pinfunction "PD15_117") (pintype "bidirectional"))
    )
    (net (code "82") (name "/SDRAM_D2") (class "Default")
      (node (ref "U2") (pin "164") (pinfunction "PD0_164") (pintype "bidirectional"))
    )
    (net (code "83") (name "/SDRAM_D3") (class "Default")
      (node (ref "U2") (pin "165") (pinfunction "PD1_165") (pintype "bidirectional"))
    )
    (net (code "84") (name "/SDRAM_D4") (class "Default")
      (node (ref "U2") (pin "79") (pinfunction "PE7_79") (pintype "bidirectional"))
    )
    (net (code "85") (name "/SDRAM_D5") (class "Default")
      (node (ref "U2") (pin "80") (pinfunction "PE8_80") (pintype "bidirectional"))
    )
    (net (code "86") (name "/SDRAM_D6") (class "Default")
      (node (ref "U2") (pin "81") (pinfunction "PE9_81") (pintype "bidirectional"))
    )
    (net (code "87") (name "/SDRAM_D7") (class "Default")
      (node (ref "U2") (pin "84") (pinfunction "PE10_84") (pintype "bidirectional"))
    )
    (net (code "88") (name "/SDRAM_D8") (class "Default")
      (node (ref "U2") (pin "85") (pinfunction "PE11_85") (pintype "bidirectional"))
    )
    (net (code "89") (name "/SDRAM_D9") (class "Default")
      (node (ref "U2") (pin "86") (pinfunction "PE12_86") (pintype "bidirectional"))
    )
    (net (code "90") (name "/SDRAM_D10") (class "Default")
      (node (ref "U2") (pin "87") (pinfunction "PE13_87") (pintype "bidirectional"))
    )
    (net (code "91") (name "/SDRAM_D11") (class "Default")
      (node (ref "U2") (pin "88") (pinfunction "PE14_88") (pintype "bidirectional"))
    )
    (net (code "92") (name "/SDRAM_D12") (class "Default")
      (node (ref "U2") (pin "89") (pinfunction "PE15_89") (pintype "bidirectional"))
    )
    (net (code "93") (name "/SDRAM_D13") (class "Default")
      (node (ref "U2") (pin "108") (pinfunction "PD8_108") (pintype "bidirectional"))
    )
    (net (code "94") (name "/SDRAM_D14") (class "Default")
      (node (ref "U2") (pin "109") (pinfunction "PD9_109") (pintype "bidirectional"))
    )
    (net (code "95") (name "/SDRAM_D15") (class "Default")
      (node (ref "U2") (pin "110") (pinfunction "PD10_110") (pintype "bidirectional"))
    )
    (net (code "96") (name "/SDRAM_D16") (class "Default")
      (node (ref "U2") (pin "98") (pinfunction "PH8_98") (pintype "bidirectional"))
    )
    (net (code "97") (name "/SDRAM_D17") (class "Default")
      (node (ref "U2") (pin "99") (pinfunction "PH9_99") (pintype "bidirectional"))
    )
    (net (code "98") (name "/SDRAM_D18") (class "Default")
      (node (ref "U2") (pin "100") (pinfunction "PH10_100") (pintype "bidirectional"))
    )
    (net (code "99") (name "/SDRAM_D19") (class "Default")
      (node (ref "U2") (pin "101") (pinfunction "PH11_101") (pintype "bidirectional"))
    )
    (net (code "100") (name "/SDRAM_D20") (class "Default")
      (node (ref "U2") (pin "102") (pinfunction "PH12_102") (pintype "bidirectional"))
    )
    (net (code "101") (name "/SDRAM_D21") (class "Default")
      (node (ref "U2") (pin "151") (pinfunction "PH13_151") (pintype "bidirectional"))
    )
    (net (code "102") (name "/SDRAM_D22") (class "Default")
      (node (ref "U2") (pin "152") (pinfunction "PH14_152") (pintype "bidirectional"))
    )
    (net (code "103") (name "/SDRAM_D23") (class "Default")
      (node (ref "U2") (pin "153") (pinfunction "PH15_153") (pintype "bidirectional"))
    )
    (net (code "104") (name "/SDRAM_D24") (class "Default")
      (node (ref "U2") (pin "154") (pinfunction "PI0_154") (pintype "bidirectional"))
    )
    (net (code "105") (name "/SDRAM_D25") (class "Default")
      (node (ref "U2") (pin "155") (pinfunction "PI1_155") (pintype "bidirectional"))
    )
    (net (code "106") (name "/SDRAM_D26") (class "Default")
      (node (ref "U2") (pin "156") (pinfunction "PI2_156") (pintype "bidirectional"))
    )
    (net (code "107") (name "/SDRAM_D27") (class "Default")
      (node (ref "U2") (pin "157") (pinfunction "PI3_157") (pintype "bidirectional"))
    )
    (net (code "108") (name "/SDRAM_D28") (class "Default")
      (node (ref "U2") (pin "208") (pinfunction "PI7_208") (pintype "bidirectional"))
    )
    (net (code "109") (name "/SDRAM_D29") (class "Default")
      (node (ref "U2") (pin "7") (pinfunction "PI8_7") (pintype "bidirectional"))
    )
    (net (code "110") (name "/SDRAM_D30") (class "Default")
      (node (ref "U2") (pin "11") (pinfunction "PI9_11") (pintype "bidirectional"))
    )
    (net (code "111") (name "/SDRAM_D31") (class "Default")
      (node (ref "U2") (pin "12") (pinfunction "PI10_12") (pintype "bidirectional"))
    )
    (net (code "112") (name "/SDRAM_DQM0") (class "Default")
      (node (ref "U2") (pin "200") (pinfunction "PE0_200") (pintype "bidirectional"))
    )
    (net (code "113") (name "/SDRAM_DQM1") (class "Default")
      (node (ref "U2") (pin "201") (pinfunction "PE1_201") (pintype "bidirectional"))
    )
    (net (code "114") (name "/SDRAM_DQM2") (class "Default")
      (node (ref "U2") (pin "205") (pinfunction "PI4_205") (pintype "bidirectional"))
    )
    (net (code "115") (name "/SDRAM_DQM3") (class "Default")
      (node (ref "U2") (pin "206") (pinfunction "PI5_206") (pintype "bidirectional"))
    )
    (net (code "116") (name "/SPI1_CLK") (class "Default")
      (node (ref "U2") (pin "192") (pinfunction "PB3_192") (pintype "bidirectional"))
    )
    (net (code "117") (name "/SPI1_MISO") (class "Default")
      (node (ref "U2") (pin "193") (pinfunction "PB4_193") (pintype "bidirectional"))
    )
    (net (code "118") (name "/SPI1_MOSI") (class "Default")
      (node (ref "U2") (pin "194") (pinfunction "PB5_194") (pintype "bidirectional"))
    )
    (net (code "119") (name "/USART1_CK") (class "Default")
      (node (ref "U2") (pin "142") (pinfunction "PA8_142") (pintype "bidirectional"))
    )
    (net (code "120") (name "/USART1_RX") (class "Default")
      (node (ref "U2") (pin "196") (pinfunction "PB7_196") (pintype "bidirectional"))
    )
    (net (code "121") (name "/USART1_TX") (class "Default")
      (node (ref "U2") (pin "195") (pinfunction "PB6_195") (pintype "bidirectional"))
    )
    (net (code "122") (name "/USART3_RX") (class "Default")
      (node (ref "U2") (pin "91") (pinfunction "PB11_91") (pintype "bidirectional"))
    )
    (net (code "123") (name "/USART3_TX") (class "Default")
      (node (ref "U2") (pin "90") (pinfunction "PB10_90") (pintype "bidirectional"))
    )
    (net (code "124") (name "/cfg0") (class "Default")
      (node (ref "J11") (pin "2") (pinfunction "2_2") (pintype "bidirectional"))
      (node (ref "R69") (pin "1") (pinfunction "1_1") (pintype "passive"))
      (node (ref "U2") (pin "27") (pinfunction "PF6_27") (pintype "bidirectional"))
    )
    (net (code "125") (name "/cfg1") (class "Default")
      (node (ref "J12") (pin "2") (pinfunction "2_2") (pintype "bidirectional"))
      (node (ref "R71") (pin "1") (pinfunction "1_1") (pintype "passive"))
      (node (ref "U2") (pin "28") (pinfunction "PF7_28") (pintype "bidirectional"))
    )
    (net (code "126") (name "/cfg2") (class "Default")
      (node (ref "J13") (pin "2") (pinfunction "2_2") (pintype "bidirectional"))
      (node (ref "R73") (pin "1") (pinfunction "1_1") (pintype "passive"))
      (node (ref "U2") (pin "29") (pinfunction "PF8_29") (pintype "bidirectional"))
    )
    (net (code "127") (name "/cfg3") (class "Default")
      (node (ref "J14") (pin "2") (pinfunction "2_2") (pintype "bidirectional"))
      (node (ref "R75") (pin "1") (pinfunction "1_1") (pintype "passive"))
      (node (ref "U2") (pin "30") (pinfunction "PF9_30") (pintype "bidirectional"))
    )
    (net (code "128") (name "/uC_off") (class "Default")
      (node (ref "U2") (pin "175") (pinfunction "PJ13_175") (pintype "bidirectional"))
    )
    (net (code "129") (name "3V3 Digital AD7768, PGA") (class "Default")
      (node (ref "C103") (pin "1") (pinfunction "1_1") (pintype "passive"))
      (node (ref "R101") (pin "2") (pinfunction "2_2") (pintype "passive"))
      (node (ref "R94") (pin "1") (pinfunction "1_1") (pintype "passive"))
      (node (ref "Y2") (pin "4") (pinfunction "VCC_4") (pintype "power_in"))
    )
    (net (code "130") (name "3V3 Digital MCU") (class "Default")
      (node (ref "C45") (pin "2") (pinfunction "2_2") (pintype "passive"))
      (node (ref "R106") (pin "2") (pinfunction "2_2") (pintype "passive"))
      (node (ref "R69") (pin "2") (pinfunction "2_2") (pintype "passive"))
      (node (ref "R71") (pin "2") (pinfunction "2_2") (pintype "passive"))
      (node (ref "R73") (pin "2") (pinfunction "2_2") (pintype "passive"))
      (node (ref "R75") (pin "2") (pinfunction "2_2") (pintype "passive"))
      (node (ref "R92") (pin "2") (pinfunction "2_2") (pintype "passive"))
      (node (ref "U2") (pin "103") (pinfunction "VDD_103") (pintype "power_in"))
      (node (ref "U2") (pin "115") (pinfunction "VDD_115") (pintype "power_in"))
      (node (ref "U2") (pin "124") (pinfunction "VDD_124") (pintype "power_in"))
      (node (ref "U2") (pin "137") (pinfunction "VDDUSB_137") (pintype "power_in"))
      (node (ref "U2") (pin "15") (pinfunction "VDD_15") (pintype "power_in"))
      (node (ref "U2") (pin "150") (pinfunction "VDD_150") (pintype "power_in"))
      (node (ref "U2") (pin "158") (pinfunction "VDD_158") (pintype "power_in"))
      (node (ref "U2") (pin "171") (pinfunction "VDD_171") (pintype "power_in"))
      (node (ref "U2") (pin "185") (pinfunction "VDD_185") (pintype "power_in"))
      (node (ref "U2") (pin "204") (pinfunction "VDD_204") (pintype "power_in"))
      (node (ref "U2") (pin "26") (pinfunction "VDD_26") (pintype "power_in"))
      (node (ref "U2") (pin "39") (pinfunction "VDD_39") (pintype "power_in"))
      (node (ref "U2") (pin "52") (pinfunction "VDD_52") (pintype "power_in"))
      (node (ref "U2") (pin "59") (pinfunction "VDD_59") (pintype "power_in"))
      (node (ref "U2") (pin "6") (pinfunction "VBAT_6") (pintype "power_in"))
      (node (ref "U2") (pin "73") (pinfunction "VDD_73") (pintype "power_in"))
      (node (ref "U2") (pin "83") (pinfunction "VDD_83") (pintype "power_in"))
      (node (ref "U2") (pin "94") (pinfunction "VDD_94") (pintype "power_in"))
    )
    (net (code "131") (name "3V3 Digital SDRAM") (class "Default")
      (node (ref "R98") (pin "2") (pinfunction "2_2") (pintype "passive"))
    )
    (net (code "132") (name "5Vin") (class "Default")
      (node (ref "C111") (pin "2") (pinfunction "2_2") (pintype "passive"))
      (node (ref "C116") (pin "2") (pinfunction "2_2") (pintype "passive"))
      (node (ref "C130") (pin "2") (pinfunction "2_2") (pintype "passive"))
      (node (ref "C60") (pin "2") (pinfunction "2_2") (pintype "passive"))
      (node (ref "R100") (pin "1") (pinfunction "1_1") (pintype "passive"))
      (node (ref "R105") (pin "1") (pinfunction "1_1") (pintype "passive"))
      (node (ref "R93") (pin "1") (pinfunction "1_1") (pintype "passive"))
      (node (ref "R97") (pin "1") (pinfunction "1_1") (pintype "passive"))
      (node (ref "U12") (pin "6") (pinfunction "VDD_6") (pintype "power_in"))
      (node (ref "U14") (pin "6") (pinfunction "VDD_6") (pintype "power_in"))
      (node (ref "U16") (pin "6") (pinfunction "VDD_6") (pintype "power_in"))
      (node (ref "U8") (pin "6") (pinfunction "VDD_6") (pintype "power_in"))
    )
    (net (code "133") (name "AGND") (class "Default")
      (node (ref "C42") (pin "1") (pinfunction "1_1") (pintype "passive"))
    )
    (net (code "134") (name "GND") (class "Default")
      (node (ref "C102") (pin "1") (pinfunction "1_1") (pintype "passive"))
      (node (ref "C103") (pin "2") (pinfunction "2_2") (pintype "passive"))
      (node (ref "C111") (pin "1") (pinfunction "1_1") (pintype "passive"))
      (node (ref "C115") (pin "1") (pinfunction "1_1") (pintype "passive"))
      (node (ref "C116") (pin "1") (pinfunction "1_1") (pintype "passive"))
      (node (ref "C117") (pin "1") (pinfunction "1_1") (pintype "passive"))
      (node (ref "C130") (pin "1") (pinfunction "1_1") (pintype "passive"))
      (node (ref "C132") (pin "1") (pinfunction "1_1") (pintype "passive"))
      (node (ref "C26") (pin "1") (pinfunction "1_1") (pintype "passive"))
      (node (ref "C27") (pin "1") (pinfunction "1_1") (pintype "passive"))
      (node (ref "C28") (pin "1") (pinfunction "1_1") (pintype "passive"))
      (node (ref "C29") (pin "1") (pinfunction "1_1") (pintype "passive"))
      (node (ref "C30") (pin "1") (pinfunction "1_1") (pintype "passive"))
      (node (ref "C31") (pin "1") (pinfunction "1_1") (pintype "passive"))
      (node (ref "C32") (pin "1") (pinfunction "1_1") (pintype "passive"))
      (node (ref "C33") (pin "1") (pinfunction "1_1") (pintype "passive"))
      (node (ref "C34") (pin "1") (pinfunction "1_1") (pintype "passive"))
      (node (ref "C35") (pin "1") (pinfunction "1_1") (pintype "passive"))
      (node (ref "C36") (pin "1") (pinfunction "1_1") (pintype "passive"))
      (node (ref "C37") (pin "1") (pinfunction "1_1") (pintype "passive"))
      (node (ref "C38") (pin "1") (pinfunction "1_1") (pintype "passive"))
      (node (ref "C39") (pin "1") (pinfunction "1_1") (pintype "passive"))
      (node (ref "C40") (pin "1") (pinfunction "1_1") (pintype "passive"))
      (node (ref "C41") (pin "1") (pinfunction "1_1") (pintype "passive"))
      (node (ref "C43") (pin "2") (pinfunction "2_2") (pintype "passive"))
      (node (ref "C44") (pin "2") (pinfunction "2_2") (pintype "passive"))
      (node (ref "C45") (pin "1") (pinfunction "1_1") (pintype "passive"))
      (node (ref "C60") (pin "1") (pinfunction "1_1") (pintype "passive"))
      (node (ref "D1") (pin "1") (pinfunction "C_1") (pintype "passive"))
      (node (ref "D2") (pin "1") (pinfunction "C_1") (pintype "passive"))
      (node (ref "D3") (pin "1") (pinfunction "C_1") (pintype "passive"))
      (node (ref "D8") (pin "1") (pinfunction "C_1") (pintype "passive"))
      (node (ref "J11") (pin "1") (pinfunction "1_1") (pintype "bidirectional"))
      (node (ref "J12") (pin "1") (pinfunction "1_1") (pintype "bidirectional"))
      (node (ref "J13") (pin "1") (pinfunction "1_1") (pintype "bidirectional"))
      (node (ref "J14") (pin "1") (pinfunction "1_1") (pintype "bidirectional"))
      (node (ref "J17") (pin "3") (pinfunction "3_3") (pintype "bidirectional"))
      (node (ref "R103") (pin "1") (pinfunction "1_1") (pintype "passive"))
      (node (ref "R107") (pin "1") (pinfunction "1_1") (pintype "passive"))
      (node (ref "R96") (pin "1") (pinfunction "1_1") (pintype "passive"))
      (node (ref "R99") (pin "1") (pinfunction "1_1") (pintype "passive"))
      (node (ref "U12") (pin "2") (pinfunction "GND_2") (pintype "power_in"))
      (node (ref "U14") (pin "2") (pinfunction "GND_2") (pintype "power_in"))
      (node (ref "U16") (pin "2") (pinfunction "GND_2") (pintype "power_in"))
      (node (ref "U2") (pin "114") (pinfunction "VSS_114") (pintype "power_in"))
      (node (ref "U2") (pin "125") (pinfunction "VSS_125") (pintype "power_in"))
      (node (ref "U2") (pin "136") (pinfunction "VSS_136") (pintype "power_in"))
      (node (ref "U2") (pin "14") (pinfunction "VSS_14") (pintype "power_in"))
      (node (ref "U2") (pin "149") (pinfunction "VSS_149") (pintype "power_in"))
      (node (ref "U2") (pin "170") (pinfunction "VSS_170") (pintype "power_in"))
      (node (ref "U2") (pin "184") (pinfunction "VSS_184") (pintype "power_in"))
      (node (ref "U2") (pin "202") (pinfunction "VSS_202") (pintype "power_in"))
      (node (ref "U2") (pin "203") (pinfunction "PDR_ON_203") (pintype "bidirectional"))
      (node (ref "U2") (pin "25") (pinfunction "VSS_25") (pintype "power_in"))
      (node (ref "U2") (pin "40") (pinfunction "VSSA_40") (pintype "power_in"))
      (node (ref "U2") (pin "51") (pinfunction "VSS_51") (pintype "power_in"))
      (node (ref "U2") (pin "60") (pinfunction "VSS_60") (pintype "power_in"))
      (node (ref "U2") (pin "72") (pinfunction "VSS_72") (pintype "power_in"))
      (node (ref "U2") (pin "82") (pinfunction "VSS_82") (pintype "power_in"))
      (node (ref "U2") (pin "93") (pinfunction "VSS_93") (pintype "power_in"))
      (node (ref "U8") (pin "2") (pinfunction "GND_2") (pintype "power_in"))
      (node (ref "Y2") (pin "2") (pinfunction "GND_2") (pintype "power_in"))
    )
    (net (code "135") (name "MCU_AVDD") (class "Default")
      (node (ref "C42") (pin "2") (pinfunction "2_2") (pintype "passive"))
      (node (ref "U2") (pin "41") (pinfunction "VREF+_41") (pintype "power_in"))
      (node (ref "U2") (pin "42") (pinfunction "VDDA_42") (pintype "power_in"))
    )
    (net (code "136") (name "MCU_VDD") (class "Default")
      (node (ref "C26") (pin "2") (pinfunction "2_2") (pintype "passive"))
      (node (ref "C27") (pin "2") (pinfunction "2_2") (pintype "passive"))
      (node (ref "C28") (pin "2") (pinfunction "2_2") (pintype "passive"))
      (node (ref "C29") (pin "2") (pinfunction "2_2") (pintype "passive"))
      (node (ref "C30") (pin "2") (pinfunction "2_2") (pintype "passive"))
      (node (ref "C31") (pin "2") (pinfunction "2_2") (pintype "passive"))
      (node (ref "C32") (pin "2") (pinfunction "2_2") (pintype "passive"))
      (node (ref "C33") (pin "2") (pinfunction "2_2") (pintype "passive"))
      (node (ref "C34") (pin "2") (pinfunction "2_2") (pintype "passive"))
      (node (ref "C35") (pin "2") (pinfunction "2_2") (pintype "passive"))
      (node (ref "C36") (pin "2") (pinfunction "2_2") (pintype "passive"))
      (node (ref "C37") (pin "2") (pinfunction "2_2") (pintype "passive"))
      (node (ref "C38") (pin "2") (pinfunction "2_2") (pintype "passive"))
      (node (ref "C39") (pin "2") (pinfunction "2_2") (pintype "passive"))
      (node (ref "C40") (pin "2") (pinfunction "2_2") (pintype "passive"))
      (node (ref "C41") (pin "2") (pinfunction "2_2") (pintype "passive"))
    )
    (net (code "137") (name "Net-(D1-A)") (class "Default")
      (node (ref "D1") (pin "2") (pinfunction "A_2") (pintype "passive"))
      (node (ref "R32") (pin "1") (pinfunction "1_1") (pintype "passive"))
    )
    (net (code "138") (name "Net-(D2-A)") (class "Default")
      (node (ref "D2") (pin "2") (pinfunction "A_2") (pintype "passive"))
      (node (ref "R34") (pin "1") (pinfunction "1_1") (pintype "passive"))
    )
    (net (code "139") (name "Net-(D3-A)") (class "Default")
      (node (ref "D3") (pin "2") (pinfunction "A_2") (pintype "passive"))
      (node (ref "R35") (pin "1") (pinfunction "1_1") (pintype "passive"))
    )
    (net (code "140") (name "Net-(D8-A)") (class "Default")
      (node (ref "D8") (pin "2") (pinfunction "A_2") (pintype "passive"))
      (node (ref "R63") (pin "1") (pinfunction "1_1") (pintype "passive"))
    )
    (net (code "141") (name "Net-(U2A-PC14)") (class "Default")
      (node (ref "U2") (pin "9") (pinfunction "PC14_9") (pintype "bidirectional"))
      (node (ref "Y2") (pin "3") (pinfunction "OUTPUT_3") (pintype "output"))
    )
    (net (code "142") (name "Net-(U2B-PE2)") (class "Default")
      (node (ref "R32") (pin "2") (pinfunction "2_2") (pintype "passive"))
      (node (ref "U2") (pin "1") (pinfunction "PE2_1") (pintype "bidirectional"))
    )
    (net (code "143") (name "Net-(U2B-PE3)") (class "Default")
      (node (ref "R34") (pin "2") (pinfunction "2_2") (pintype "passive"))
      (node (ref "U2") (pin "2") (pinfunction "PE3_2") (pintype "bidirectional"))
    )
    (net (code "144") (name "Net-(U2B-PE4)") (class "Default")
      (node (ref "R35") (pin "2") (pinfunction "2_2") (pintype "passive"))
      (node (ref "U2") (pin "3") (pinfunction "PE4_3") (pintype "bidirectional"))
    )
    (net (code "145") (name "Net-(U2B-PE5)") (class "Default")
      (node (ref "R63") (pin "2") (pinfunction "2_2") (pintype "passive"))
      (node (ref "U2") (pin "4") (pinfunction "PE5_4") (pintype "bidirectional"))
    )
    (net (code "146") (name "Net-(U2D-VCAP_1)") (class "Default")
      (node (ref "C43") (pin "1") (pinfunction "1_1") (pintype "passive"))
      (node (ref "U2") (pin "92") (pinfunction "VCAP_1_92") (pintype "power_in"))
    )
    (net (code "147") (name "Net-(U2D-VCAP_2)") (class "Default")
      (node (ref "C44") (pin "1") (pinfunction "1_1") (pintype "passive"))
      (node (ref "U2") (pin "148") (pinfunction "VCAP_2_148") (pintype "power_in"))
    )
    (net (code "148") (name "Net-(U8-CT)") (class "Default")
      (node (ref "R93") (pin "2") (pinfunction "2_2") (pintype "passive"))
      (node (ref "U8") (pin "4") (pinfunction "CT_4") (pintype "passive"))
    )
    (net (code "149") (name "Net-(U8-SENSE)") (class "Default")
      (node (ref "C102") (pin "2") (pinfunction "2_2") (pintype "passive"))
      (node (ref "R95") (pin "1") (pinfunction "1_1") (pintype "passive"))
      (node (ref "R96") (pin "2") (pinfunction "2_2") (pintype "passive"))
      (node (ref "U8") (pin "5") (pinfunction "SENSE_5") (pintype "input"))
    )
    (net (code "150") (name "Net-(U12-CT)") (class "Default")
      (node (ref "R97") (pin "2") (pinfunction "2_2") (pintype "passive"))
      (node (ref "U12") (pin "4") (pinfunction "CT_4") (pintype "passive"))
    )
    (net (code "151") (name "Net-(U12-SENSE)") (class "Default")
      (node (ref "C115") (pin "2") (pinfunction "2_2") (pintype "passive"))
      (node (ref "R98") (pin "1") (pinfunction "1_1") (pintype "passive"))
      (node (ref "R99") (pin "2") (pinfunction "2_2") (pintype "passive"))
      (node (ref "U12") (pin "5") (pinfunction "SENSE_5") (pintype "input"))
    )
    (net (code "152") (name "Net-(U12-~{MR})") (class "Default")
      (node (ref "U12") (pin "3") (pinfunction "~{MR}_3") (pintype "input"))
      (node (ref "U14") (pin "1") (pinfunction "~{RESET}_1") (pintype "open_collector"))
    )
    (net (code "153") (name "Net-(U12-~{RESET})") (class "Default")
      (node (ref "U12") (pin "1") (pinfunction "~{RESET}_1") (pintype "open_collector"))
      (node (ref "U8") (pin "3") (pinfunction "~{MR}_3") (pintype "input"))
    )
    (net (code "154") (name "Net-(U14-CT)") (class "Default")
      (node (ref "R100") (pin "2") (pinfunction "2_2") (pintype "passive"))
      (node (ref "U14") (pin "4") (pinfunction "CT_4") (pintype "passive"))
    )
    (net (code "155") (name "Net-(U14-SENSE)") (class "Default")
      (node (ref "C117") (pin "2") (pinfunction "2_2") (pintype "passive"))
      (node (ref "R101") (pin "1") (pinfunction "1_1") (pintype "passive"))
      (node (ref "R103") (pin "2") (pinfunction "2_2") (pintype "passive"))
      (node (ref "U14") (pin "5") (pinfunction "SENSE_5") (pintype "input"))
    )
    (net (code "156") (name "Net-(U14-~{MR})") (class "Default")
      (node (ref "U14") (pin "3") (pinfunction "~{MR}_3") (pintype "input"))
      (node (ref "U16") (pin "1") (pinfunction "~{RESET}_1") (pintype "open_collector"))
    )
    (net (code "157") (name "Net-(U16-CT)") (class "Default")
      (node (ref "R105") (pin "2") (pinfunction "2_2") (pintype "passive"))
      (node (ref "U16") (pin "4") (pinfunction "CT_4") (pintype "passive"))
    )
    (net (code "158") (name "Net-(U16-SENSE)") (class "Default")
      (node (ref "C132") (pin "2") (pinfunction "2_2") (pintype "passive"))
      (node (ref "R106") (pin "1") (pinfunction "1_1") (pintype "passive"))
      (node (ref "R107") (pin "2") (pinfunction "2_2") (pintype "passive"))
      (node (ref "U16") (pin "5") (pinfunction "SENSE_5") (pintype "input"))
    )
    (net (code "159") (name "Net-(Y2-EOH)") (class "Default")
      (node (ref "R94") (pin "2") (pinfunction "2_2") (pintype "passive"))
      (node (ref "Y2") (pin "1") (pinfunction "EOH_1") (pintype "input"))
    )
    (net (code "160") (name "unconnected-(U2A-PA0-Pad43)") (class "Default")
      (node (ref "U2") (pin "43") (pinfunction "PA0_43") (pintype "bidirectional"))
    )
    (net (code "161") (name "unconnected-(U2A-PA3-Pad50)") (class "Default")
      (node (ref "U2") (pin "50") (pinfunction "PA3_50") (pintype "bidirectional"))
    )
    (net (code "162") (name "unconnected-(U2A-PA4-Pad53)") (class "Default")
      (node (ref "U2") (pin "53") (pinfunction "PA4_53") (pintype "bidirectional"))
    )
    (net (code "163") (name "unconnected-(U2A-PA5-Pad54)") (class "Default")
      (node (ref "U2") (pin "54") (pinfunction "PA5_54") (pintype "bidirectional"))
    )
    (net (code "164") (name "unconnected-(U2A-PA6-Pad55)") (class "Default")
      (node (ref "U2") (pin "55") (pinfunction "PA6_55") (pintype "bidirectional"))
    )
    (net (code "165") (name "unconnected-(U2A-PA9-Pad143)") (class "Default")
      (node (ref "U2") (pin "143") (pinfunction "PA9_143") (pintype "bidirectional"))
    )
    (net (code "166") (name "unconnected-(U2A-PA15-Pad160)") (class "Default")
      (node (ref "U2") (pin "160") (pinfunction "PA15_160") (pintype "bidirectional"))
    )
    (net (code "167") (name "unconnected-(U2A-PB0-Pad61)") (class "Default")
      (node (ref "U2") (pin "61") (pinfunction "PB0_61") (pintype "bidirectional"))
    )
    (net (code "168") (name "unconnected-(U2A-PB1-Pad62)") (class "Default")
      (node (ref "U2") (pin "62") (pinfunction "PB1_62") (pintype "bidirectional"))
    )
    (net (code "169") (name "unconnected-(U2A-PB2-Pad63)") (class "Default")
      (node (ref "U2") (pin "63") (pinfunction "PB2_63") (pintype "bidirectional"))
    )
    (net (code "170") (name "unconnected-(U2A-PB8-Pad198)") (class "Default")
      (node (ref "U2") (pin "198") (pinfunction "PB8_198") (pintype "bidirectional"))
    )
    (net (code "171") (name "unconnected-(U2A-PB9-Pad199)") (class "Default")
      (node (ref "U2") (pin "199") (pinfunction "PB9_199") (pintype "bidirectional"))
    )
    (net (code "172") (name "unconnected-(U2A-PB12-Pad104)") (class "Default")
      (node (ref "U2") (pin "104") (pinfunction "PB12_104") (pintype "bidirectional"))
    )
    (net (code "173") (name "unconnected-(U2A-PB13-Pad105)") (class "Default")
      (node (ref "U2") (pin "105") (pinfunction "PB13_105") (pintype "bidirectional"))
    )
    (net (code "174") (name "unconnected-(U2A-PB14-Pad106)") (class "Default")
      (node (ref "U2") (pin "106") (pinfunction "PB14_106") (pintype "bidirectional"))
    )
    (net (code "175") (name "unconnected-(U2A-PB15-Pad107)") (class "Default")
      (node (ref "U2") (pin "107") (pinfunction "PB15_107") (pintype "bidirectional"))
    )
    (net (code "176") (name "unconnected-(U2A-PC2-Pad37)") (class "Default")
      (node (ref "U2") (pin "37") (pinfunction "PC2_37") (pintype "bidirectional"))
    )
    (net (code "177") (name "unconnected-(U2A-PC15-Pad10)") (class "Default")
      (node (ref "U2") (pin "10") (pinfunction "PC15_10") (pintype "bidirectional"))
    )
    (net (code "178") (name "unconnected-(U2A-PD11-Pad111)") (class "Default")
      (node (ref "U2") (pin "111") (pinfunction "PD11_111") (pintype "bidirectional"))
    )
    (net (code "179") (name "unconnected-(U2A-PD12-Pad112)") (class "Default")
      (node (ref "U2") (pin "112") (pinfunction "PD12_112") (pintype "bidirectional"))
    )
    (net (code "180") (name "unconnected-(U2A-PD13-Pad113)") (class "Default")
      (node (ref "U2") (pin "113") (pinfunction "PD13_113") (pintype "bidirectional"))
    )
    (net (code "181") (name "unconnected-(U2B-PE6-Pad5)") (class "Default")
      (node (ref "U2") (pin "5") (pinfunction "PE6_5") (pintype "bidirectional"))
    )
    (net (code "182") (name "unconnected-(U2B-PF10-Pad31)") (class "Default")
      (node (ref "U2") (pin "31") (pinfunction "PF10_31") (pintype "bidirectional"))
    )
    (net (code "183") (name "unconnected-(U2B-PG2-Pad129)") (class "Default")
      (node (ref "U2") (pin "129") (pinfunction "PG2_129") (pintype "bidirectional"))
    )
    (net (code "184") (name "unconnected-(U2B-PG3-Pad130)") (class "Default")
      (node (ref "U2") (pin "130") (pinfunction "PG3_130") (pintype "bidirectional"))
    )
    (net (code "185") (name "unconnected-(U2B-PG6-Pad133)") (class "Default")
      (node (ref "U2") (pin "133") (pinfunction "PG6_133") (pintype "bidirectional"))
    )
    (net (code "186") (name "unconnected-(U2B-PG7-Pad134)") (class "Default")
      (node (ref "U2") (pin "134") (pinfunction "PG7_134") (pintype "bidirectional"))
    )
    (net (code "187") (name "unconnected-(U2B-PG9-Pad178)") (class "Default")
      (node (ref "U2") (pin "178") (pinfunction "PG9_178") (pintype "bidirectional"))
    )
    (net (code "188") (name "unconnected-(U2B-PG10-Pad179)") (class "Default")
      (node (ref "U2") (pin "179") (pinfunction "PG10_179") (pintype "bidirectional"))
    )
    (net (code "189") (name "unconnected-(U2B-PG12-Pad181)") (class "Default")
      (node (ref "U2") (pin "181") (pinfunction "PG12_181") (pintype "bidirectional"))
    )
    (net (code "190") (name "unconnected-(U2B-PH0-Pad32)") (class "Default")
      (node (ref "U2") (pin "32") (pinfunction "PH0_32") (pintype "bidirectional"))
    )
    (net (code "191") (name "unconnected-(U2B-PH1-Pad33)") (class "Default")
      (node (ref "U2") (pin "33") (pinfunction "PH1_33") (pintype "bidirectional"))
    )
    (net (code "192") (name "unconnected-(U2B-PH3-Pad47)") (class "Default")
      (node (ref "U2") (pin "47") (pinfunction "PH3_47") (pintype "bidirectional"))
    )
    (net (code "193") (name "unconnected-(U2B-PH4-Pad48)") (class "Default")
      (node (ref "U2") (pin "48") (pinfunction "PH4_48") (pintype "bidirectional"))
    )
    (net (code "194") (name "unconnected-(U2B-PH5-Pad49)") (class "Default")
      (node (ref "U2") (pin "49") (pinfunction "PH5_49") (pintype "bidirectional"))
    )
    (net (code "195") (name "unconnected-(U2B-PH6-Pad96)") (class "Default")
      (node (ref "U2") (pin "96") (pinfunction "PH6_96") (pintype "bidirectional"))
    )
    (net (code "196") (name "unconnected-(U2B-PH7-Pad97)") (class "Default")
      (node (ref "U2") (pin "97") (pinfunction "PH7_97") (pintype "bidirectional"))
    )
    (net (code "197") (name "unconnected-(U2C-BOOT0-Pad197)") (class "Default")
      (node (ref "U2") (pin "197") (pinfunction "BOOT0_197") (pintype "input"))
    )
    (net (code "198") (name "unconnected-(U16-~{MR}-Pad3)") (class "Default")
      (node (ref "U16") (pin "3") (pinfunction "~{MR}_3") (pintype "input"))
    )
  )
)
